# ADF4351.net
KiCad netlist of a schematic drawn in Altium Designer
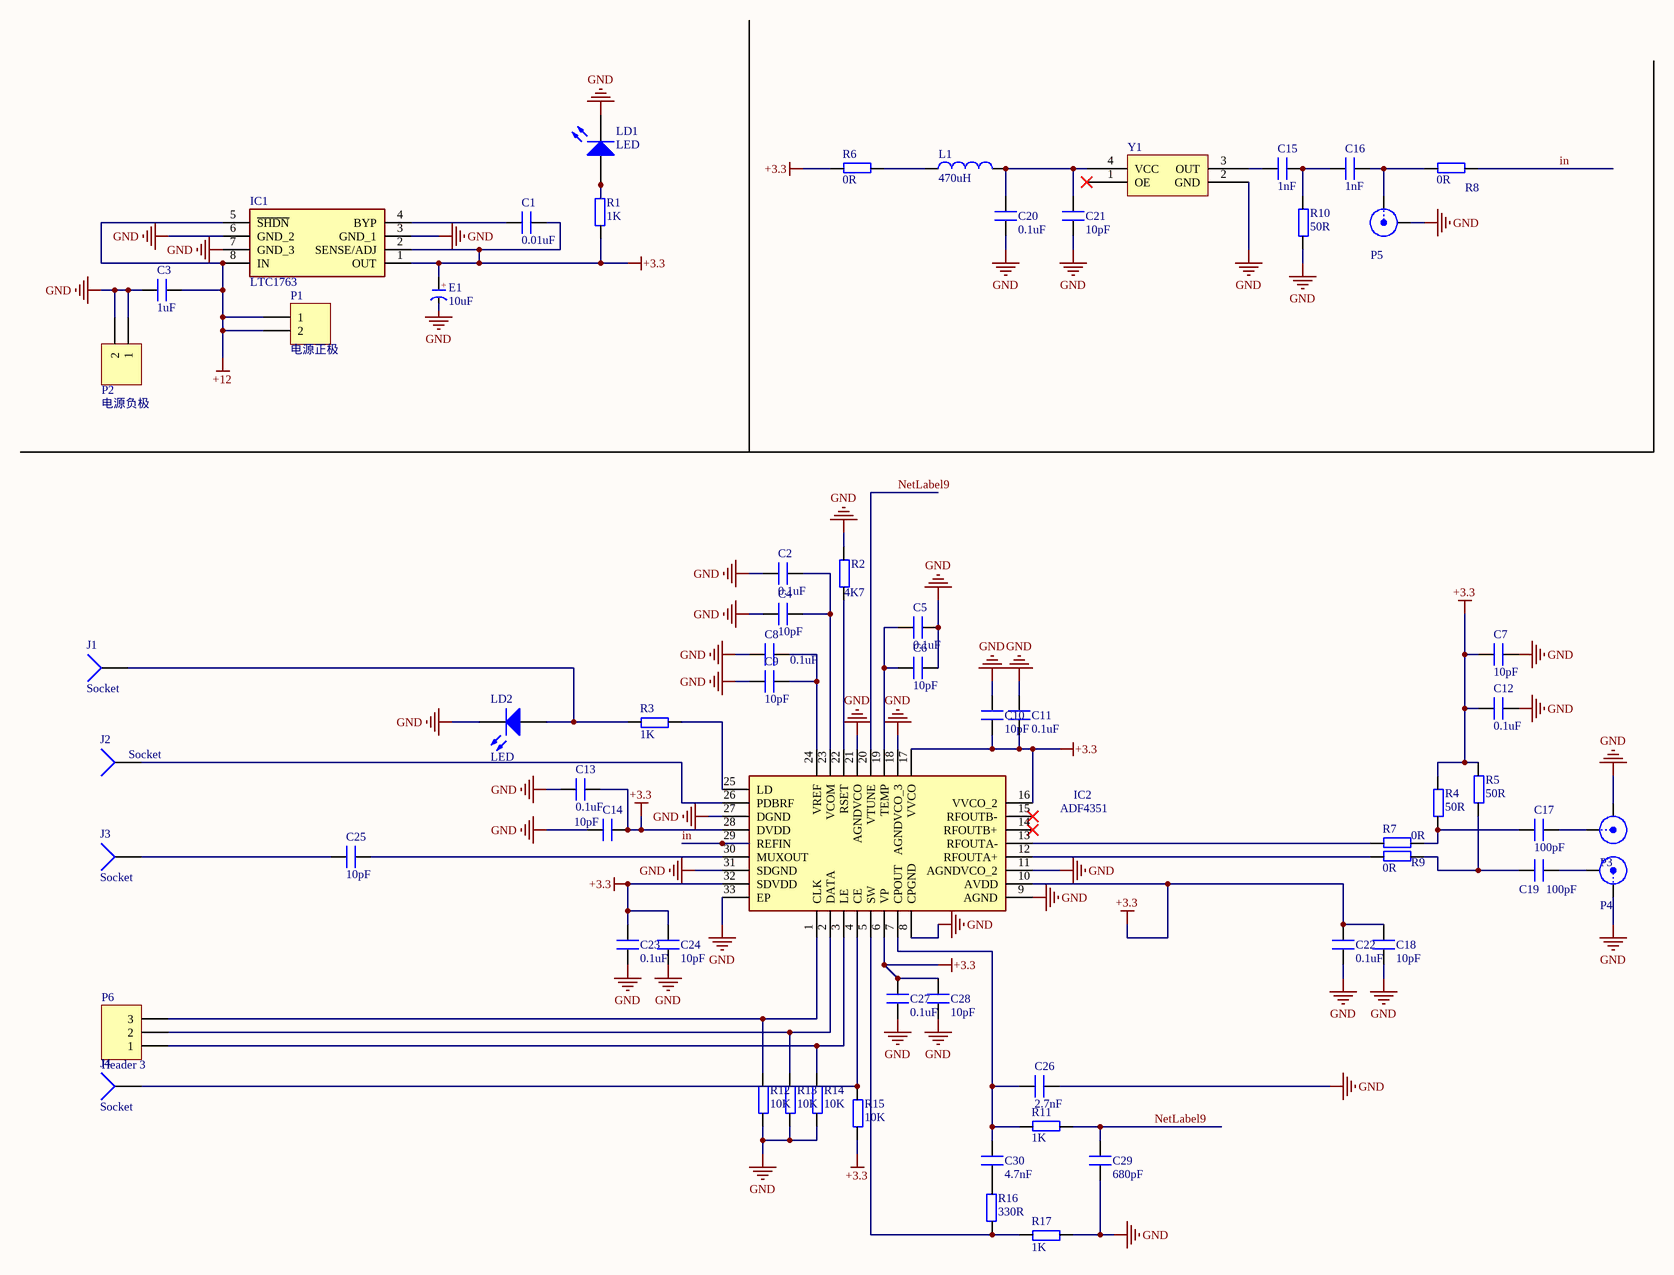
[diagram p0: ADF4351原理图(改).SchDoc]

(export (version "E")
  (design (tool "Eeschema 10.0.6"))
  (components
    (comp (ref "C1")
      (value "0.01uF")
      (footprint "0603C")
      (description "Capacitor")
      (libsource (lib "MYLIB") (part "C"))
    )
    (comp (ref "C2")
      (value "0.1uF")
      (footprint "0603C")
      (description "Capacitor")
      (libsource (lib "MYLIB") (part "C"))
    )
    (comp (ref "C3")
      (value "1uF")
      (footprint "0603C")
      (description "Capacitor")
      (libsource (lib "MYLIB") (part "C"))
    )
    (comp (ref "C4")
      (value "10pF")
      (footprint "0603C")
      (description "Capacitor")
      (libsource (lib "MYLIB") (part "C"))
    )
    (comp (ref "C5")
      (value "0.1uF")
      (footprint "0603C")
      (description "Capacitor")
      (libsource (lib "MYLIB") (part "C"))
    )
    (comp (ref "C6")
      (value "10pF")
      (footprint "0603C")
      (description "Capacitor")
      (libsource (lib "MYLIB") (part "C"))
    )
    (comp (ref "C7")
      (value "10pF")
      (footprint "0603C")
      (description "Capacitor")
      (libsource (lib "MYLIB") (part "C"))
    )
    (comp (ref "C8")
      (value "0.1uF")
      (footprint "0603C")
      (description "Capacitor")
      (libsource (lib "MYLIB") (part "C"))
    )
    (comp (ref "C9")
      (value "10pF")
      (footprint "0603C")
      (description "Capacitor")
      (libsource (lib "MYLIB") (part "C"))
    )
    (comp (ref "C10")
      (value "10pF")
      (footprint "0603C")
      (description "Capacitor")
      (libsource (lib "MYLIB") (part "C"))
    )
    (comp (ref "C11")
      (value "0.1uF")
      (footprint "0603C")
      (description "Capacitor")
      (libsource (lib "MYLIB") (part "C"))
    )
    (comp (ref "C12")
      (value "0.1uF")
      (footprint "0603C")
      (description "Capacitor")
      (libsource (lib "MYLIB") (part "C"))
    )
    (comp (ref "C13")
      (value "0.1uF")
      (footprint "0603C")
      (description "Capacitor")
      (libsource (lib "MYLIB") (part "C"))
    )
    (comp (ref "C14")
      (value "10pF")
      (footprint "0603C")
      (description "Capacitor")
      (libsource (lib "MYLIB") (part "C"))
    )
    (comp (ref "C15")
      (value "1nF")
      (footprint "0603C")
      (description "Capacitor")
      (libsource (lib "MYLIB") (part "C"))
    )
    (comp (ref "C16")
      (value "1nF")
      (footprint "0603C")
      (description "Capacitor")
      (libsource (lib "MYLIB") (part "C"))
    )
    (comp (ref "C17")
      (value "100pF")
      (footprint "0603C")
      (description "Capacitor")
      (libsource (lib "MYLIB") (part "C"))
    )
    (comp (ref "C18")
      (value "10pF")
      (footprint "0603C")
      (description "Capacitor")
      (libsource (lib "MYLIB") (part "C"))
    )
    (comp (ref "C19")
      (value "100pF")
      (footprint "0603C")
      (description "Capacitor")
      (libsource (lib "MYLIB") (part "C"))
    )
    (comp (ref "C20")
      (value "0.1uF")
      (footprint "0603C")
      (description "Capacitor")
      (libsource (lib "MYLIB") (part "C"))
    )
    (comp (ref "C21")
      (value "10pF")
      (footprint "0603C")
      (description "Capacitor")
      (libsource (lib "MYLIB") (part "C"))
    )
    (comp (ref "C22")
      (value "0.1uF")
      (footprint "0603C")
      (description "Capacitor")
      (libsource (lib "MYLIB") (part "C"))
    )
    (comp (ref "C23")
      (value "0.1uF")
      (footprint "0603C")
      (description "Capacitor")
      (libsource (lib "MYLIB") (part "C"))
    )
    (comp (ref "C24")
      (value "10pF")
      (footprint "0603C")
      (description "Capacitor")
      (libsource (lib "MYLIB") (part "C"))
    )
    (comp (ref "C25")
      (value "10pF")
      (footprint "0603C")
      (description "Capacitor")
      (libsource (lib "MYLIB") (part "C"))
    )
    (comp (ref "C26")
      (value "2.7nF")
      (footprint "0603C")
      (description "Capacitor")
      (libsource (lib "MYLIB") (part "C"))
    )
    (comp (ref "C27")
      (value "0.1uF")
      (footprint "0603C")
      (description "Capacitor")
      (libsource (lib "MYLIB") (part "C"))
    )
    (comp (ref "C28")
      (value "10pF")
      (footprint "0603C")
      (description "Capacitor")
      (libsource (lib "MYLIB") (part "C"))
    )
    (comp (ref "C29")
      (value "680pF")
      (footprint "0603C")
      (description "Capacitor")
      (libsource (lib "MYLIB") (part "C"))
    )
    (comp (ref "C30")
      (value "4.7nF")
      (footprint "0603C")
      (description "Capacitor")
      (libsource (lib "MYLIB") (part "C"))
    )
    (comp (ref "E1")
      (value "10uF")
      (footprint "CAP 1.5*4*8")
      (description "直插电解电容")
      (fields (field (name "版权归属") "源创客"))
      (libsource (lib "MYLIB") (part "C-CAP"))
    )
    (comp (ref "IC1")
      (value "LTC1763")
      (footprint "MYLIB:SOIC8_1R27_4R9X6")
      (description "Integrated Circuit")
      (fields (field (name "MANUFACTURER_PART_NUMBER") "LTC1763CS8-3.3#TRPBF"))
      (libsource (lib "MYLIB") (part "LTC1763CS8-3.3#TRPBF"))
    )
    (comp (ref "IC2")
      (value "ADF4351")
      (footprint "MYLIB:QFN50P500X500X100-33N")
      (description "Integrated Circuit")
      (fields
        (field (name "MOUSER2 PART NUMBER") "584-ADF4351BCPZ")
        (field (name "MANUFACTURER_PART_NUMBER") "ADF4351BCPZ")
      )
      (libsource (lib "MYLIB") (part "ADF4351BCPZ"))
    )
    (comp (ref "J1")
      (value "Socket")
      (footprint "PIN1")
      (fields (field (name "PUBLISHER") "Altium Limited"))
      (libsource (lib "Miscellaneous Connectors") (part "Socket"))
    )
    (comp (ref "J2")
      (value "Socket")
      (footprint "PIN1")
      (fields (field (name "PUBLISHER") "Altium Limited"))
      (libsource (lib "Miscellaneous Connectors") (part "Socket"))
    )
    (comp (ref "J3")
      (value "Socket")
      (footprint "PIN1")
      (fields (field (name "PUBLISHER") "Altium Limited"))
      (libsource (lib "Miscellaneous Connectors") (part "Socket"))
    )
    (comp (ref "J4")
      (value "Socket")
      (footprint "PIN1")
      (fields (field (name "PUBLISHER") "Altium Limited"))
      (libsource (lib "Miscellaneous Connectors") (part "Socket"))
    )
    (comp (ref "L1")
      (value "470uH")
      (footprint "0603C")
      (description "Inductor")
      (fields (field (name "PUBLISHER") "Altium Limited"))
      (libsource (lib "MYLIB") (part "Inductor"))
    )
    (comp (ref "LD1")
      (value "LED")
      (footprint "SMDLED")
      (description "Typical RED, GREEN, YELLOW, AMBER GaAs LED")
      (fields (field (name "PUBLISHER") "Altium Limited"))
      (libsource (lib "MYLIB") (part "LED"))
    )
    (comp (ref "LD2")
      (value "LED")
      (footprint "SMDLED")
      (description "Typical RED, GREEN, YELLOW, AMBER GaAs LED")
      (fields (field (name "PUBLISHER") "Altium Limited"))
      (libsource (lib "MYLIB") (part "LED"))
    )
    (comp (ref "P1")
      (value "电源正极")
      (footprint "HDR1X2")
      (description "Header, 2-Pin")
      (fields (field (name "PUBLISHER") "Altium Limited"))
      (libsource (lib "") (part "Header 2_1"))
    )
    (comp (ref "P2")
      (value "电源负极")
      (footprint "HDR1X2")
      (description "Header, 2-Pin")
      (fields (field (name "PUBLISHER") "Altium Limited"))
      (libsource (lib "MYLIB") (part "Header 2"))
    )
    (comp (ref "P3")
      (value "SMA")
      (footprint "SMA-V")
      (description "SMA Connector")
      (libsource (lib "MYLIB") (part "SMA"))
    )
    (comp (ref "P4")
      (value "SMA")
      (footprint "SMA-V")
      (description "SMA Connector")
      (libsource (lib "MYLIB") (part "SMA"))
    )
    (comp (ref "P5")
      (value "SMA")
      (footprint "SMA-V")
      (description "SMA Connector")
      (libsource (lib "MYLIB") (part "SMA"))
    )
    (comp (ref "P6")
      (value "Header 3")
      (footprint "HDR1X3")
      (description "Header, 3-Pin")
      (fields (field (name "PUBLISHER") "Altium Limited"))
      (libsource (lib "Miscellaneous Connectors") (part "Header 3"))
    )
    (comp (ref "R1")
      (value "1K")
      (footprint "电阻:RS 1/4W")
      (description "Resistor")
      (libsource (lib "MYLIB") (part "Resistor"))
    )
    (comp (ref "R2")
      (value "4K7")
      (footprint "0603R")
      (description "Resistor")
      (libsource (lib "MYLIB") (part "Resistor"))
    )
    (comp (ref "R3")
      (value "1K")
      (footprint "0603R")
      (description "Resistor")
      (libsource (lib "MYLIB") (part "Resistor"))
    )
    (comp (ref "R4")
      (value "50R")
      (footprint "0603R")
      (description "Resistor")
      (libsource (lib "MYLIB") (part "Resistor"))
    )
    (comp (ref "R5")
      (value "50R")
      (footprint "0603R")
      (description "Resistor")
      (libsource (lib "MYLIB") (part "Resistor"))
    )
    (comp (ref "R6")
      (value "0R")
      (footprint "0603R")
      (description "Resistor")
      (libsource (lib "MYLIB") (part "Resistor"))
    )
    (comp (ref "R7")
      (value "0R")
      (footprint "0603R")
      (description "Resistor")
      (libsource (lib "MYLIB") (part "Resistor"))
    )
    (comp (ref "R8")
      (value "0R")
      (footprint "0603R")
      (description "Resistor")
      (libsource (lib "MYLIB") (part "Resistor"))
    )
    (comp (ref "R9")
      (value "0R")
      (footprint "0603R")
      (description "Resistor")
      (libsource (lib "MYLIB") (part "Resistor"))
    )
    (comp (ref "R10")
      (value "50R")
      (footprint "0603R")
      (description "Resistor")
      (libsource (lib "MYLIB") (part "Resistor"))
    )
    (comp (ref "R11")
      (value "1K")
      (footprint "0603R")
      (description "Resistor")
      (libsource (lib "MYLIB") (part "Resistor"))
    )
    (comp (ref "R12")
      (value "10K")
      (footprint "0603R")
      (description "Resistor")
      (libsource (lib "MYLIB") (part "Resistor"))
    )
    (comp (ref "R13")
      (value "10K")
      (footprint "0603R")
      (description "Resistor")
      (libsource (lib "MYLIB") (part "Resistor"))
    )
    (comp (ref "R14")
      (value "10K")
      (footprint "0603R")
      (description "Resistor")
      (libsource (lib "MYLIB") (part "Resistor"))
    )
    (comp (ref "R15")
      (value "10K")
      (footprint "0603R")
      (description "Resistor")
      (libsource (lib "MYLIB") (part "Resistor"))
    )
    (comp (ref "R16")
      (value "330R")
      (footprint "0603R")
      (description "Resistor")
      (libsource (lib "MYLIB") (part "Resistor"))
    )
    (comp (ref "R17")
      (value "1K")
      (footprint "0603R")
      (description "Resistor")
      (libsource (lib "MYLIB") (part "Resistor"))
    )
    (comp (ref "Y1")
      (value "~")
      (footprint "XTAL-OCX7050")
      (description "Simple Package Xtal Oscillator")
      (libsource (lib "MYLIB") (part "XTAL-SPXO"))
    )
  )
  (nets
    (net (code "1") (name "+3.3") (class "Default")
      (node (ref "C1") (pin "2") (pintype "passive"))
      (node (ref "C10") (pin "1") (pintype "passive"))
      (node (ref "C11") (pin "1") (pintype "passive"))
      (node (ref "C12") (pin "1") (pintype "passive"))
      (node (ref "C13") (pin "1") (pintype "passive"))
      (node (ref "C14") (pin "1") (pintype "passive"))
      (node (ref "C18") (pin "1") (pintype "passive"))
      (node (ref "C22") (pin "1") (pintype "passive"))
      (node (ref "C23") (pin "1") (pintype "passive"))
      (node (ref "C24") (pin "1") (pintype "passive"))
      (node (ref "C27") (pin "1") (pintype "passive"))
      (node (ref "C28") (pin "1") (pintype "passive"))
      (node (ref "C7") (pin "1") (pintype "passive"))
      (node (ref "E1") (pin "1") (pinfunction "A_1") (pintype "passive"))
      (node (ref "IC1") (pin "1") (pinfunction "OUT_1") (pintype "passive"))
      (node (ref "IC1") (pin "2") (pinfunction "SENSE/ADJ_2") (pintype "passive"))
      (node (ref "IC2") (pin "10") (pinfunction "AVDD_10") (pintype "passive"))
      (node (ref "IC2") (pin "16") (pinfunction "VVCO_2_16") (pintype "passive"))
      (node (ref "IC2") (pin "17") (pinfunction "VVCO_17") (pintype "passive"))
      (node (ref "IC2") (pin "28") (pinfunction "DVDD_28") (pintype "passive"))
      (node (ref "IC2") (pin "32") (pinfunction "SDVDD_32") (pintype "passive"))
      (node (ref "IC2") (pin "6") (pinfunction "VP_6") (pintype "passive"))
      (node (ref "R1") (pin "2") (pintype "passive"))
      (node (ref "R15") (pin "1") (pintype "passive"))
      (node (ref "R4") (pin "2") (pintype "passive"))
      (node (ref "R5") (pin "2") (pintype "passive"))
      (node (ref "R6") (pin "2") (pintype "passive"))
    )
    (net (code "2") (name "+12") (class "Default")
      (node (ref "C3") (pin "2") (pintype "passive"))
      (node (ref "IC1") (pin "5") (pinfunction "~{SHDN}_5") (pintype "passive"))
      (node (ref "IC1") (pin "8") (pinfunction "IN_8") (pintype "passive"))
      (node (ref "P1") (pin "1") (pinfunction "1_1") (pintype "passive"))
      (node (ref "P1") (pin "2") (pinfunction "2_2") (pintype "passive"))
    )
    (net (code "3") (name "/NetLabel9") (class "Default")
      (node (ref "C29") (pin "1") (pintype "passive"))
      (node (ref "IC2") (pin "20") (pinfunction "VTUNE_20") (pintype "passive"))
      (node (ref "R11") (pin "1") (pintype "passive"))
    )
    (net (code "4") (name "/in") (class "Default")
      (node (ref "IC2") (pin "29") (pinfunction "REFIN_29") (pintype "passive"))
      (node (ref "R8") (pin "1") (pintype "passive"))
    )
    (net (code "5") (name "GND") (class "Default")
      (node (ref "C10") (pin "2") (pintype "passive"))
      (node (ref "C11") (pin "2") (pintype "passive"))
      (node (ref "C12") (pin "2") (pintype "passive"))
      (node (ref "C13") (pin "2") (pintype "passive"))
      (node (ref "C14") (pin "2") (pintype "passive"))
      (node (ref "C18") (pin "2") (pintype "passive"))
      (node (ref "C2") (pin "2") (pintype "passive"))
      (node (ref "C20") (pin "2") (pintype "passive"))
      (node (ref "C21") (pin "2") (pintype "passive"))
      (node (ref "C22") (pin "2") (pintype "passive"))
      (node (ref "C23") (pin "2") (pintype "passive"))
      (node (ref "C24") (pin "2") (pintype "passive"))
      (node (ref "C26") (pin "2") (pintype "passive"))
      (node (ref "C27") (pin "2") (pintype "passive"))
      (node (ref "C28") (pin "2") (pintype "passive"))
      (node (ref "C29") (pin "2") (pintype "passive"))
      (node (ref "C3") (pin "1") (pintype "passive"))
      (node (ref "C4") (pin "2") (pintype "passive"))
      (node (ref "C5") (pin "1") (pintype "passive"))
      (node (ref "C6") (pin "1") (pintype "passive"))
      (node (ref "C7") (pin "2") (pintype "passive"))
      (node (ref "C8") (pin "2") (pintype "passive"))
      (node (ref "C9") (pin "2") (pintype "passive"))
      (node (ref "E1") (pin "2") (pinfunction "K_2") (pintype "passive"))
      (node (ref "IC1") (pin "3") (pinfunction "GND_1_3") (pintype "passive"))
      (node (ref "IC1") (pin "6") (pinfunction "GND_2_6") (pintype "passive"))
      (node (ref "IC1") (pin "7") (pinfunction "GND_3_7") (pintype "passive"))
      (node (ref "IC2") (pin "11") (pinfunction "AGNDVCO_2_11") (pintype "passive"))
      (node (ref "IC2") (pin "18") (pinfunction "AGNDVCO_3_18") (pintype "passive"))
      (node (ref "IC2") (pin "21") (pinfunction "AGNDVCO_21") (pintype "passive"))
      (node (ref "IC2") (pin "27") (pinfunction "DGND_27") (pintype "passive"))
      (node (ref "IC2") (pin "31") (pinfunction "SDGND_31") (pintype "passive"))
      (node (ref "IC2") (pin "33") (pinfunction "EP_33") (pintype "passive"))
      (node (ref "IC2") (pin "8") (pinfunction "CPGND_8") (pintype "passive"))
      (node (ref "IC2") (pin "9") (pinfunction "AGND_9") (pintype "passive"))
      (node (ref "LD1") (pin "2") (pinfunction "K_2") (pintype "passive"))
      (node (ref "LD2") (pin "2") (pinfunction "K_2") (pintype "passive"))
      (node (ref "P2") (pin "1") (pinfunction "1_1") (pintype "passive"))
      (node (ref "P2") (pin "2") (pinfunction "2_2") (pintype "passive"))
      (node (ref "P3") (pin "2") (pinfunction "Y_2") (pintype "passive"))
      (node (ref "P4") (pin "1") (pinfunction "X_1") (pintype "passive"))
      (node (ref "P5") (pin "2") (pinfunction "Y_2") (pintype "passive"))
      (node (ref "R10") (pin "1") (pintype "passive"))
      (node (ref "R12") (pin "1") (pintype "passive"))
      (node (ref "R13") (pin "1") (pintype "passive"))
      (node (ref "R14") (pin "1") (pintype "passive"))
      (node (ref "R17") (pin "2") (pintype "passive"))
      (node (ref "R2") (pin "2") (pintype "passive"))
      (node (ref "Y1") (pin "2") (pinfunction "GND_2") (pintype "passive"))
    )
    (net (code "6") (name "Net-(C15-Pad1)") (class "Default")
      (node (ref "C15") (pin "1") (pintype "passive"))
      (node (ref "C16") (pin "2") (pintype "passive"))
      (node (ref "R10") (pin "2") (pintype "passive"))
    )
    (net (code "7") (name "Net-(C17-Pad1)") (class "Default")
      (node (ref "C17") (pin "1") (pintype "passive"))
      (node (ref "R4") (pin "1") (pintype "passive"))
      (node (ref "R7") (pin "1") (pintype "passive"))
    )
    (net (code "8") (name "Net-(C19-Pad1)") (class "Default")
      (node (ref "C19") (pin "1") (pintype "passive"))
      (node (ref "R5") (pin "1") (pintype "passive"))
      (node (ref "R9") (pin "1") (pintype "passive"))
    )
    (net (code "9") (name "Net-(C25-Pad1)") (class "Default")
      (node (ref "C25") (pin "1") (pintype "passive"))
      (node (ref "J3") (pin "1") (pinfunction "1_1") (pintype "passive"))
    )
    (net (code "10") (name "Net-(C30-Pad1)") (class "Default")
      (node (ref "C30") (pin "1") (pintype "passive"))
      (node (ref "R16") (pin "1") (pintype "passive"))
    )
    (net (code "11") (name "Net-(IC1-BYP)") (class "Default")
      (node (ref "C1") (pin "1") (pintype "passive"))
      (node (ref "IC1") (pin "4") (pinfunction "BYP_4") (pintype "passive"))
    )
    (net (code "12") (name "Net-(IC2-CE)") (class "Default")
      (node (ref "IC2") (pin "4") (pinfunction "CE_4") (pintype "passive"))
      (node (ref "J4") (pin "1") (pinfunction "1_1") (pintype "passive"))
      (node (ref "R15") (pin "2") (pintype "passive"))
    )
    (net (code "13") (name "Net-(IC2-CLK)") (class "Default")
      (node (ref "IC2") (pin "1") (pinfunction "CLK_1") (pintype "passive"))
      (node (ref "P6") (pin "3") (pinfunction "3_3") (pintype "passive"))
      (node (ref "R12") (pin "2") (pintype "passive"))
    )
    (net (code "14") (name "Net-(IC2-CPOUT)") (class "Default")
      (node (ref "C26") (pin "1") (pintype "passive"))
      (node (ref "C30") (pin "2") (pintype "passive"))
      (node (ref "IC2") (pin "7") (pinfunction "CPOUT_7") (pintype "passive"))
      (node (ref "R11") (pin "2") (pintype "passive"))
    )
    (net (code "15") (name "Net-(IC2-DATA)") (class "Default")
      (node (ref "IC2") (pin "2") (pinfunction "DATA_2") (pintype "passive"))
      (node (ref "P6") (pin "2") (pinfunction "2_2") (pintype "passive"))
      (node (ref "R13") (pin "2") (pintype "passive"))
    )
    (net (code "16") (name "Net-(IC2-LD)") (class "Default")
      (node (ref "IC2") (pin "25") (pinfunction "LD_25") (pintype "passive"))
      (node (ref "R3") (pin "2") (pintype "passive"))
    )
    (net (code "17") (name "Net-(IC2-LE)") (class "Default")
      (node (ref "IC2") (pin "3") (pinfunction "LE_3") (pintype "passive"))
      (node (ref "P6") (pin "1") (pinfunction "1_1") (pintype "passive"))
      (node (ref "R14") (pin "2") (pintype "passive"))
    )
    (net (code "18") (name "Net-(IC2-MUXOUT)") (class "Default")
      (node (ref "C25") (pin "2") (pintype "passive"))
      (node (ref "IC2") (pin "30") (pinfunction "MUXOUT_30") (pintype "passive"))
    )
    (net (code "19") (name "Net-(IC2-PDBRF)") (class "Default")
      (node (ref "IC2") (pin "26") (pinfunction "PDBRF_26") (pintype "passive"))
      (node (ref "J2") (pin "1") (pinfunction "1_1") (pintype "passive"))
    )
    (net (code "20") (name "Net-(IC2-RFOUTA+)") (class "Default")
      (node (ref "IC2") (pin "12") (pinfunction "RFOUTA+_12") (pintype "passive"))
      (node (ref "R9") (pin "2") (pintype "passive"))
    )
    (net (code "21") (name "Net-(IC2-RFOUTA-)") (class "Default")
      (node (ref "IC2") (pin "13") (pinfunction "RFOUTA-_13") (pintype "passive"))
      (node (ref "R7") (pin "2") (pintype "passive"))
    )
    (net (code "22") (name "Net-(IC2-RSET)") (class "Default")
      (node (ref "IC2") (pin "22") (pinfunction "RSET_22") (pintype "passive"))
      (node (ref "R2") (pin "1") (pintype "passive"))
    )
    (net (code "23") (name "Net-(IC2-SW)") (class "Default")
      (node (ref "IC2") (pin "5") (pinfunction "SW_5") (pintype "passive"))
      (node (ref "R16") (pin "2") (pintype "passive"))
      (node (ref "R17") (pin "1") (pintype "passive"))
    )
    (net (code "24") (name "Net-(IC2-TEMP)") (class "Default")
      (node (ref "C5") (pin "2") (pintype "passive"))
      (node (ref "C6") (pin "2") (pintype "passive"))
      (node (ref "IC2") (pin "19") (pinfunction "TEMP_19") (pintype "passive"))
    )
    (net (code "25") (name "Net-(IC2-VCOM)") (class "Default")
      (node (ref "C2") (pin "1") (pintype "passive"))
      (node (ref "C4") (pin "1") (pintype "passive"))
      (node (ref "IC2") (pin "23") (pinfunction "VCOM_23") (pintype "passive"))
    )
    (net (code "26") (name "Net-(IC2-VREF)") (class "Default")
      (node (ref "C8") (pin "1") (pintype "passive"))
      (node (ref "C9") (pin "1") (pintype "passive"))
      (node (ref "IC2") (pin "24") (pinfunction "VREF_24") (pintype "passive"))
    )
    (net (code "27") (name "Net-(L1-Pad1)") (class "Default")
      (node (ref "L1") (pin "1") (pinfunction "1_1") (pintype "passive"))
      (node (ref "R6") (pin "1") (pintype "passive"))
    )
    (net (code "28") (name "Net-(LD1-A)") (class "Default")
      (node (ref "LD1") (pin "1") (pinfunction "A_1") (pintype "passive"))
      (node (ref "R1") (pin "1") (pintype "passive"))
    )
    (net (code "29") (name "Net-(LD2-A)") (class "Default")
      (node (ref "J1") (pin "1") (pinfunction "1_1") (pintype "passive"))
      (node (ref "LD2") (pin "1") (pinfunction "A_1") (pintype "passive"))
      (node (ref "R3") (pin "1") (pintype "passive"))
    )
    (net (code "30") (name "Net-(P3-X)") (class "Default")
      (node (ref "C17") (pin "2") (pintype "passive"))
      (node (ref "P3") (pin "1") (pinfunction "X_1") (pintype "passive"))
    )
    (net (code "31") (name "Net-(P4-Y)") (class "Default")
      (node (ref "C19") (pin "2") (pintype "passive"))
      (node (ref "P4") (pin "2") (pinfunction "Y_2") (pintype "passive"))
    )
    (net (code "32") (name "Net-(P5-X)") (class "Default")
      (node (ref "C16") (pin "1") (pintype "passive"))
      (node (ref "P5") (pin "1") (pinfunction "X_1") (pintype "passive"))
      (node (ref "R8") (pin "2") (pintype "passive"))
    )
    (net (code "33") (name "Net-(Y1-OUT)") (class "Default")
      (node (ref "C15") (pin "2") (pintype "passive"))
      (node (ref "Y1") (pin "3") (pinfunction "OUT_3") (pintype "passive"))
    )
    (net (code "34") (name "Net-(Y1-VCC)") (class "Default")
      (node (ref "C20") (pin "1") (pintype "passive"))
      (node (ref "C21") (pin "1") (pintype "passive"))
      (node (ref "L1") (pin "2") (pinfunction "2_2") (pintype "passive"))
      (node (ref "Y1") (pin "4") (pinfunction "VCC_4") (pintype "passive"))
    )
    (net (code "35") (name "unconnected-(IC2-RFOUTB+-Pad14)") (class "Default")
      (node (ref "IC2") (pin "14") (pinfunction "RFOUTB+_14") (pintype "passive+no_connect"))
    )
    (net (code "36") (name "unconnected-(IC2-RFOUTB--Pad15)") (class "Default")
      (node (ref "IC2") (pin "15") (pinfunction "RFOUTB-_15") (pintype "passive+no_connect"))
    )
    (net (code "37") (name "unconnected-(Y1-OE-Pad1)") (class "Default")
      (node (ref "Y1") (pin "1") (pinfunction "OE_1") (pintype "passive+no_connect"))
    )
  )
)
